# AddressingMuxes_2.net
KiCad netlist of a schematic drawn in Altium Designer
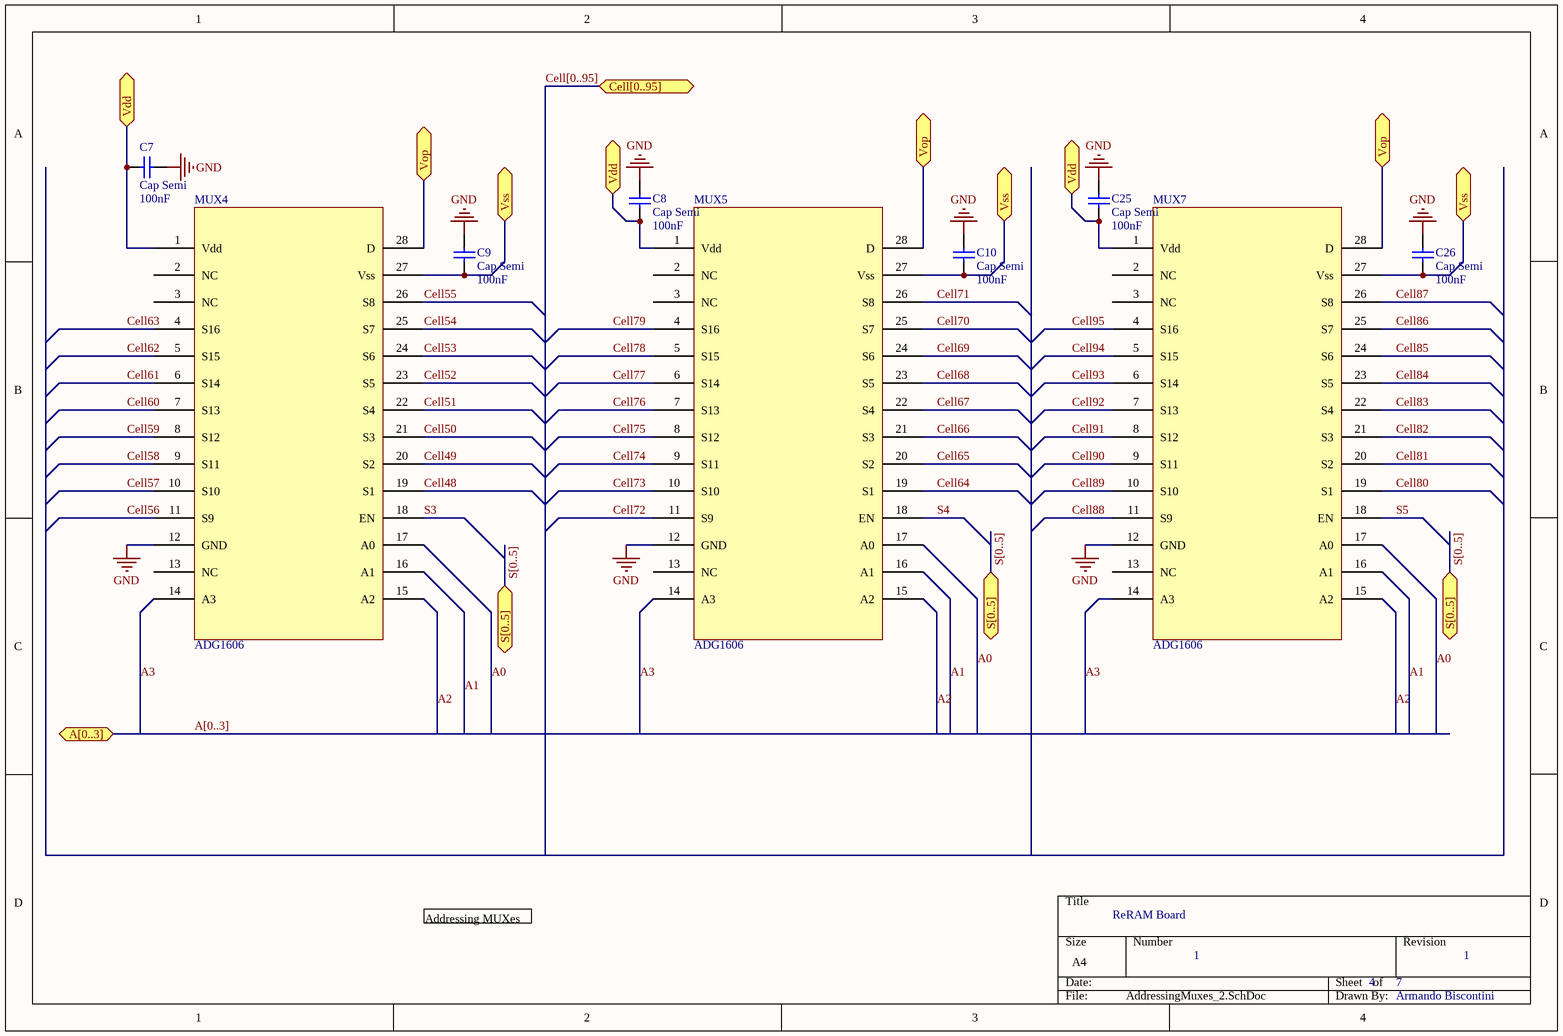
[diagram p0: AddressingMuxes_2.SchDoc]

(export (version "E")
  (design (tool "Eeschema 10.0.6"))
  (components
    (comp (ref "C7")
      (value "Cap Semi")
      (footprint "C1206")
      (description "Capacitor (Semiconductor SIM Model)")
      (fields (field (name "ALTIUM_VALUE") "100nF") (field (name "PUBLISHER") "Altium Limited"))
      (libsource (lib "Miscellaneous Devices") (part "Cap Semi"))
    )
    (comp (ref "C8")
      (value "Cap Semi")
      (footprint "C1206")
      (description "Capacitor (Semiconductor SIM Model)")
      (fields (field (name "ALTIUM_VALUE") "100nF") (field (name "PUBLISHER") "Altium Limited"))
      (libsource (lib "Miscellaneous Devices") (part "Cap Semi"))
    )
    (comp (ref "C9")
      (value "Cap Semi")
      (footprint "C1206")
      (description "Capacitor (Semiconductor SIM Model)")
      (fields (field (name "ALTIUM_VALUE") "100nF") (field (name "PUBLISHER") "Altium Limited"))
      (libsource (lib "Miscellaneous Devices") (part "Cap Semi"))
    )
    (comp (ref "C10")
      (value "Cap Semi")
      (footprint "C1206")
      (description "Capacitor (Semiconductor SIM Model)")
      (fields (field (name "ALTIUM_VALUE") "100nF") (field (name "PUBLISHER") "Altium Limited"))
      (libsource (lib "Miscellaneous Devices") (part "Cap Semi"))
    )
    (comp (ref "C25")
      (value "Cap Semi")
      (footprint "C1206")
      (description "Capacitor (Semiconductor SIM Model)")
      (fields (field (name "ALTIUM_VALUE") "100nF") (field (name "PUBLISHER") "Altium Limited"))
      (libsource (lib "Miscellaneous Devices") (part "Cap Semi"))
    )
    (comp (ref "C26")
      (value "Cap Semi")
      (footprint "C1206")
      (description "Capacitor (Semiconductor SIM Model)")
      (fields (field (name "ALTIUM_VALUE") "100nF") (field (name "PUBLISHER") "Altium Limited"))
      (libsource (lib "Miscellaneous Devices") (part "Cap Semi"))
    )
    (comp (ref "MUX4")
      (value "ADG1606")
      (footprint "TSOP65P640X120-28N")
      (description "Analog Devices ADG1606")
      (libsource (lib "ReRAM_Board_library") (part "ADG1606"))
    )
    (comp (ref "MUX5")
      (value "ADG1606")
      (footprint "TSOP65P640X120-28N")
      (description "Analog Devices ADG1606")
      (libsource (lib "ReRAM_Board_library") (part "ADG1606"))
    )
    (comp (ref "MUX7")
      (value "ADG1606")
      (footprint "TSOP65P640X120-28N")
      (description "Analog Devices ADG1606")
      (libsource (lib "ReRAM_Board_library") (part "ADG1606"))
    )
  )
  (nets
    (net (code "52") (name "/A0") (class "Default")
      (node (ref "MUX4") (pin "17") (pinfunction "A0_17") (pintype "passive"))
      (node (ref "MUX5") (pin "17") (pinfunction "A0_17") (pintype "passive"))
      (node (ref "MUX7") (pin "17") (pinfunction "A0_17") (pintype "passive"))
    )
    (net (code "53") (name "/A1") (class "Default")
      (node (ref "MUX4") (pin "16") (pinfunction "A1_16") (pintype "passive"))
      (node (ref "MUX5") (pin "16") (pinfunction "A1_16") (pintype "passive"))
      (node (ref "MUX7") (pin "16") (pinfunction "A1_16") (pintype "passive"))
    )
    (net (code "54") (name "/A2") (class "Default")
      (node (ref "MUX4") (pin "15") (pinfunction "A2_15") (pintype "passive"))
      (node (ref "MUX5") (pin "15") (pinfunction "A2_15") (pintype "passive"))
      (node (ref "MUX7") (pin "15") (pinfunction "A2_15") (pintype "passive"))
    )
    (net (code "55") (name "/A3") (class "Default")
      (node (ref "MUX4") (pin "14") (pinfunction "A3_14") (pintype "passive"))
      (node (ref "MUX5") (pin "14") (pinfunction "A3_14") (pintype "passive"))
      (node (ref "MUX7") (pin "14") (pinfunction "A3_14") (pintype "passive"))
    )
    (net (code "57") (name "/Cell48") (class "Default")
      (node (ref "MUX4") (pin "19") (pinfunction "S1_19") (pintype "passive"))
    )
    (net (code "58") (name "/Cell49") (class "Default")
      (node (ref "MUX4") (pin "20") (pinfunction "S2_20") (pintype "passive"))
    )
    (net (code "59") (name "/Cell50") (class "Default")
      (node (ref "MUX4") (pin "21") (pinfunction "S3_21") (pintype "passive"))
    )
    (net (code "60") (name "/Cell51") (class "Default")
      (node (ref "MUX4") (pin "22") (pinfunction "S4_22") (pintype "passive"))
    )
    (net (code "61") (name "/Cell52") (class "Default")
      (node (ref "MUX4") (pin "23") (pinfunction "S5_23") (pintype "passive"))
    )
    (net (code "62") (name "/Cell53") (class "Default")
      (node (ref "MUX4") (pin "24") (pinfunction "S6_24") (pintype "passive"))
    )
    (net (code "63") (name "/Cell54") (class "Default")
      (node (ref "MUX4") (pin "25") (pinfunction "S7_25") (pintype "passive"))
    )
    (net (code "64") (name "/Cell55") (class "Default")
      (node (ref "MUX4") (pin "26") (pinfunction "S8_26") (pintype "passive"))
    )
    (net (code "65") (name "/Cell56") (class "Default")
      (node (ref "MUX4") (pin "11") (pinfunction "S9_11") (pintype "passive"))
    )
    (net (code "66") (name "/Cell57") (class "Default")
      (node (ref "MUX4") (pin "10") (pinfunction "S10_10") (pintype "passive"))
    )
    (net (code "67") (name "/Cell58") (class "Default")
      (node (ref "MUX4") (pin "9") (pinfunction "S11_9") (pintype "passive"))
    )
    (net (code "68") (name "/Cell59") (class "Default")
      (node (ref "MUX4") (pin "8") (pinfunction "S12_8") (pintype "passive"))
    )
    (net (code "69") (name "/Cell60") (class "Default")
      (node (ref "MUX4") (pin "7") (pinfunction "S13_7") (pintype "passive"))
    )
    (net (code "70") (name "/Cell61") (class "Default")
      (node (ref "MUX4") (pin "6") (pinfunction "S14_6") (pintype "passive"))
    )
    (net (code "71") (name "/Cell62") (class "Default")
      (node (ref "MUX4") (pin "5") (pinfunction "S15_5") (pintype "passive"))
    )
    (net (code "72") (name "/Cell63") (class "Default")
      (node (ref "MUX4") (pin "4") (pinfunction "S16_4") (pintype "passive"))
    )
    (net (code "73") (name "/Cell64") (class "Default")
      (node (ref "MUX5") (pin "19") (pinfunction "S1_19") (pintype "passive"))
    )
    (net (code "74") (name "/Cell65") (class "Default")
      (node (ref "MUX5") (pin "20") (pinfunction "S2_20") (pintype "passive"))
    )
    (net (code "75") (name "/Cell66") (class "Default")
      (node (ref "MUX5") (pin "21") (pinfunction "S3_21") (pintype "passive"))
    )
    (net (code "76") (name "/Cell67") (class "Default")
      (node (ref "MUX5") (pin "22") (pinfunction "S4_22") (pintype "passive"))
    )
    (net (code "77") (name "/Cell68") (class "Default")
      (node (ref "MUX5") (pin "23") (pinfunction "S5_23") (pintype "passive"))
    )
    (net (code "78") (name "/Cell69") (class "Default")
      (node (ref "MUX5") (pin "24") (pinfunction "S6_24") (pintype "passive"))
    )
    (net (code "79") (name "/Cell70") (class "Default")
      (node (ref "MUX5") (pin "25") (pinfunction "S7_25") (pintype "passive"))
    )
    (net (code "80") (name "/Cell71") (class "Default")
      (node (ref "MUX5") (pin "26") (pinfunction "S8_26") (pintype "passive"))
    )
    (net (code "81") (name "/Cell72") (class "Default")
      (node (ref "MUX5") (pin "11") (pinfunction "S9_11") (pintype "passive"))
    )
    (net (code "82") (name "/Cell73") (class "Default")
      (node (ref "MUX5") (pin "10") (pinfunction "S10_10") (pintype "passive"))
    )
    (net (code "83") (name "/Cell74") (class "Default")
      (node (ref "MUX5") (pin "9") (pinfunction "S11_9") (pintype "passive"))
    )
    (net (code "84") (name "/Cell75") (class "Default")
      (node (ref "MUX5") (pin "8") (pinfunction "S12_8") (pintype "passive"))
    )
    (net (code "85") (name "/Cell76") (class "Default")
      (node (ref "MUX5") (pin "7") (pinfunction "S13_7") (pintype "passive"))
    )
    (net (code "86") (name "/Cell77") (class "Default")
      (node (ref "MUX5") (pin "6") (pinfunction "S14_6") (pintype "passive"))
    )
    (net (code "87") (name "/Cell78") (class "Default")
      (node (ref "MUX5") (pin "5") (pinfunction "S15_5") (pintype "passive"))
    )
    (net (code "88") (name "/Cell79") (class "Default")
      (node (ref "MUX5") (pin "4") (pinfunction "S16_4") (pintype "passive"))
    )
    (net (code "89") (name "/Cell80") (class "Default")
      (node (ref "MUX7") (pin "19") (pinfunction "S1_19") (pintype "passive"))
    )
    (net (code "90") (name "/Cell81") (class "Default")
      (node (ref "MUX7") (pin "20") (pinfunction "S2_20") (pintype "passive"))
    )
    (net (code "91") (name "/Cell82") (class "Default")
      (node (ref "MUX7") (pin "21") (pinfunction "S3_21") (pintype "passive"))
    )
    (net (code "92") (name "/Cell83") (class "Default")
      (node (ref "MUX7") (pin "22") (pinfunction "S4_22") (pintype "passive"))
    )
    (net (code "93") (name "/Cell84") (class "Default")
      (node (ref "MUX7") (pin "23") (pinfunction "S5_23") (pintype "passive"))
    )
    (net (code "94") (name "/Cell85") (class "Default")
      (node (ref "MUX7") (pin "24") (pinfunction "S6_24") (pintype "passive"))
    )
    (net (code "95") (name "/Cell86") (class "Default")
      (node (ref "MUX7") (pin "25") (pinfunction "S7_25") (pintype "passive"))
    )
    (net (code "96") (name "/Cell87") (class "Default")
      (node (ref "MUX7") (pin "26") (pinfunction "S8_26") (pintype "passive"))
    )
    (net (code "97") (name "/Cell88") (class "Default")
      (node (ref "MUX7") (pin "11") (pinfunction "S9_11") (pintype "passive"))
    )
    (net (code "98") (name "/Cell89") (class "Default")
      (node (ref "MUX7") (pin "10") (pinfunction "S10_10") (pintype "passive"))
    )
    (net (code "99") (name "/Cell90") (class "Default")
      (node (ref "MUX7") (pin "9") (pinfunction "S11_9") (pintype "passive"))
    )
    (net (code "100") (name "/Cell91") (class "Default")
      (node (ref "MUX7") (pin "8") (pinfunction "S12_8") (pintype "passive"))
    )
    (net (code "101") (name "/Cell92") (class "Default")
      (node (ref "MUX7") (pin "7") (pinfunction "S13_7") (pintype "passive"))
    )
    (net (code "102") (name "/Cell93") (class "Default")
      (node (ref "MUX7") (pin "6") (pinfunction "S14_6") (pintype "passive"))
    )
    (net (code "103") (name "/Cell94") (class "Default")
      (node (ref "MUX7") (pin "5") (pinfunction "S15_5") (pintype "passive"))
    )
    (net (code "104") (name "/Cell95") (class "Default")
      (node (ref "MUX7") (pin "4") (pinfunction "S16_4") (pintype "passive"))
    )
    (net (code "106") (name "/S3") (class "Default")
      (node (ref "MUX4") (pin "18") (pinfunction "EN_18") (pintype "passive"))
    )
    (net (code "107") (name "/S4") (class "Default")
      (node (ref "MUX5") (pin "18") (pinfunction "EN_18") (pintype "passive"))
    )
    (net (code "108") (name "/S5") (class "Default")
      (node (ref "MUX7") (pin "18") (pinfunction "EN_18") (pintype "passive"))
    )
    (net (code "110") (name "/Vdd") (class "Default")
      (node (ref "C25") (pin "2") (pinfunction "2_2") (pintype "passive"))
      (node (ref "C7") (pin "1") (pinfunction "1_1") (pintype "passive"))
      (node (ref "C8") (pin "2") (pinfunction "2_2") (pintype "passive"))
      (node (ref "MUX4") (pin "1") (pinfunction "Vdd_1") (pintype "passive"))
      (node (ref "MUX5") (pin "1") (pinfunction "Vdd_1") (pintype "passive"))
      (node (ref "MUX7") (pin "1") (pinfunction "Vdd_1") (pintype "passive"))
    )
    (net (code "111") (name "/Vop") (class "Default")
      (node (ref "MUX4") (pin "28") (pinfunction "D_28") (pintype "passive"))
      (node (ref "MUX5") (pin "28") (pinfunction "D_28") (pintype "passive"))
      (node (ref "MUX7") (pin "28") (pinfunction "D_28") (pintype "passive"))
    )
    (net (code "112") (name "/Vss") (class "Default")
      (node (ref "C10") (pin "2") (pinfunction "2_2") (pintype "passive"))
      (node (ref "C26") (pin "2") (pinfunction "2_2") (pintype "passive"))
      (node (ref "C9") (pin "2") (pinfunction "2_2") (pintype "passive"))
      (node (ref "MUX4") (pin "27") (pinfunction "Vss_27") (pintype "passive"))
      (node (ref "MUX5") (pin "27") (pinfunction "Vss_27") (pintype "passive"))
      (node (ref "MUX7") (pin "27") (pinfunction "Vss_27") (pintype "passive"))
    )
    (net (code "113") (name "GND") (class "Default")
      (node (ref "C10") (pin "1") (pinfunction "1_1") (pintype "passive"))
      (node (ref "C25") (pin "1") (pinfunction "1_1") (pintype "passive"))
      (node (ref "C26") (pin "1") (pinfunction "1_1") (pintype "passive"))
      (node (ref "C7") (pin "2") (pinfunction "2_2") (pintype "passive"))
      (node (ref "C8") (pin "1") (pinfunction "1_1") (pintype "passive"))
      (node (ref "C9") (pin "1") (pinfunction "1_1") (pintype "passive"))
      (node (ref "MUX4") (pin "12") (pinfunction "GND_12") (pintype "passive"))
      (node (ref "MUX5") (pin "12") (pinfunction "GND_12") (pintype "passive"))
      (node (ref "MUX7") (pin "12") (pinfunction "GND_12") (pintype "passive"))
    )
    (net (code "114") (name "unconnected-(MUX4-NC-Pad2)") (class "Default")
      (node (ref "MUX4") (pin "2") (pinfunction "NC_2") (pintype "passive"))
    )
    (net (code "115") (name "unconnected-(MUX4-NC-Pad3)") (class "Default")
      (node (ref "MUX4") (pin "3") (pinfunction "NC_3") (pintype "passive"))
    )
    (net (code "116") (name "unconnected-(MUX4-NC-Pad13)") (class "Default")
      (node (ref "MUX4") (pin "13") (pinfunction "NC_13") (pintype "passive"))
    )
    (net (code "117") (name "unconnected-(MUX5-NC-Pad2)") (class "Default")
      (node (ref "MUX5") (pin "2") (pinfunction "NC_2") (pintype "passive"))
    )
    (net (code "118") (name "unconnected-(MUX5-NC-Pad3)") (class "Default")
      (node (ref "MUX5") (pin "3") (pinfunction "NC_3") (pintype "passive"))
    )
    (net (code "119") (name "unconnected-(MUX5-NC-Pad13)") (class "Default")
      (node (ref "MUX5") (pin "13") (pinfunction "NC_13") (pintype "passive"))
    )
    (net (code "120") (name "unconnected-(MUX7-NC-Pad2)") (class "Default")
      (node (ref "MUX7") (pin "2") (pinfunction "NC_2") (pintype "passive"))
    )
    (net (code "121") (name "unconnected-(MUX7-NC-Pad3)") (class "Default")
      (node (ref "MUX7") (pin "3") (pinfunction "NC_3") (pintype "passive"))
    )
    (net (code "122") (name "unconnected-(MUX7-NC-Pad13)") (class "Default")
      (node (ref "MUX7") (pin "13") (pinfunction "NC_13") (pintype "passive"))
    )
  )
)
